# mc.net
KiCad netlist of a schematic drawn in EAGLE
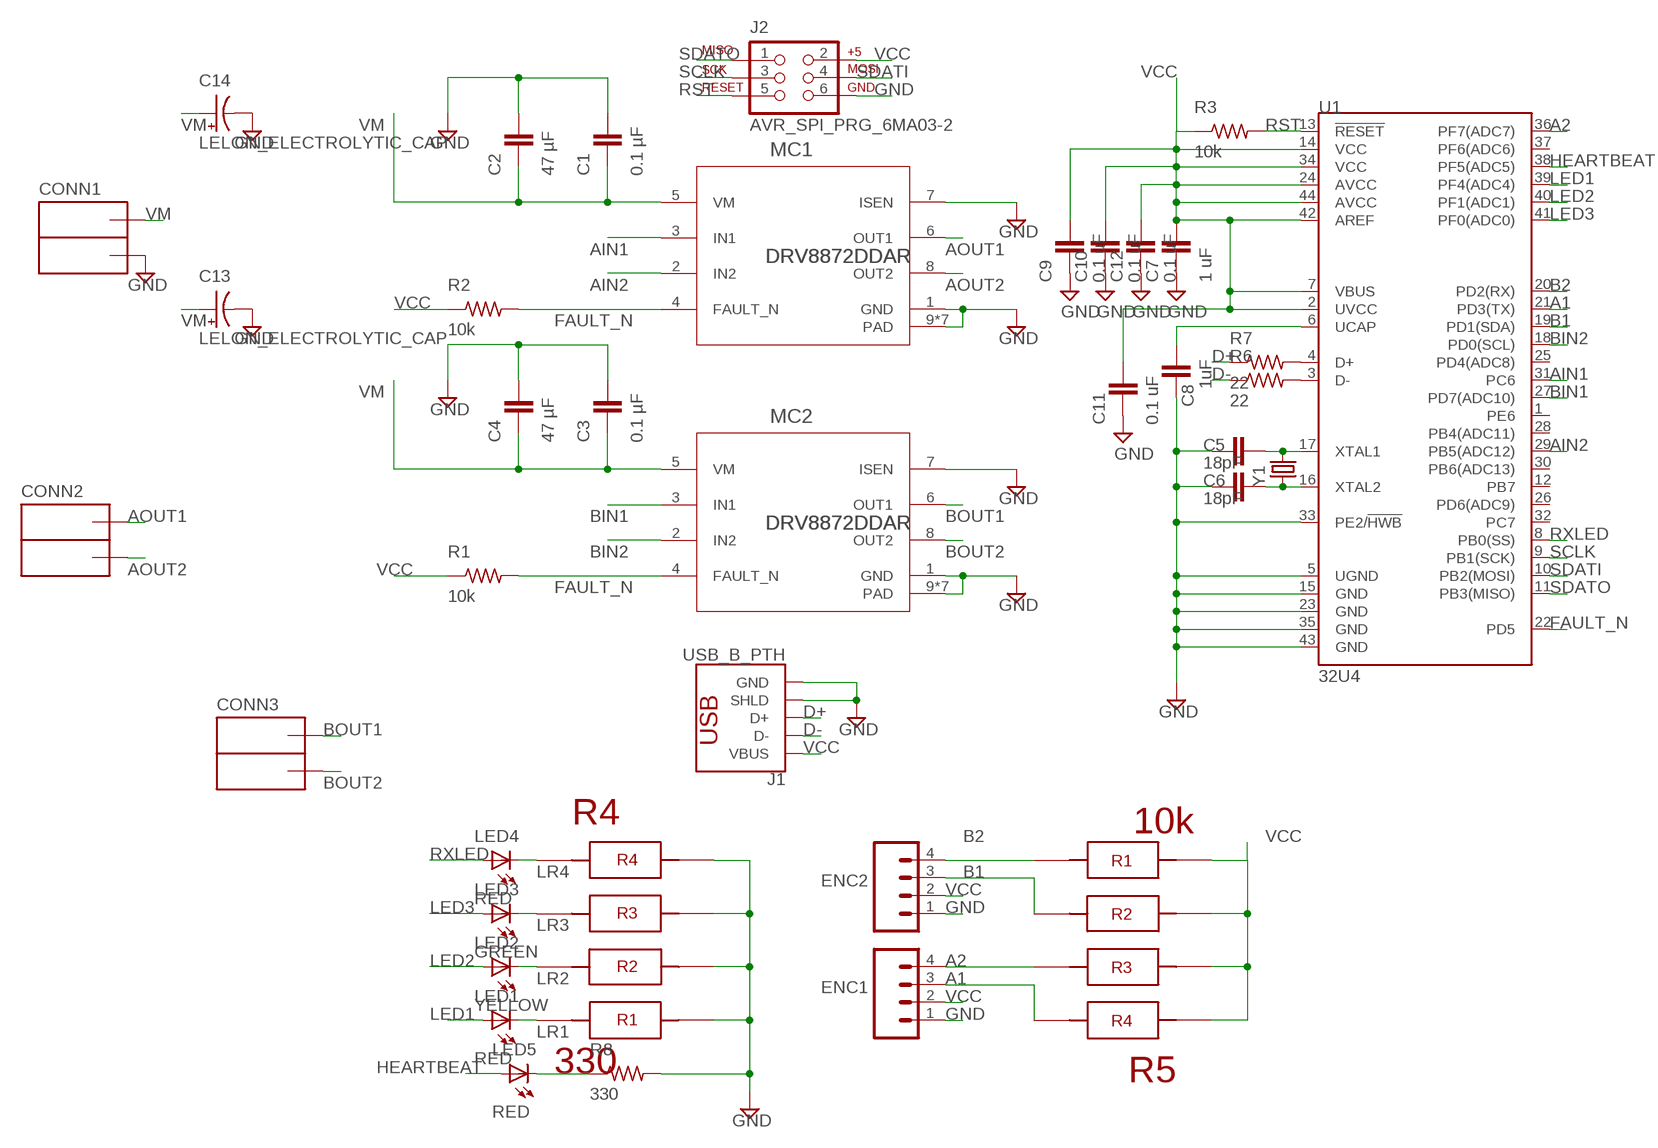
[diagram p0: schematic, sheet 1]

(export (version "E")
  (design (tool "Eeschema 10.0.6"))
  (components
    (comp (ref "C1")
      (value "0.1 µF")
      (footprint "eagle-import:0603-CAP")
      (libsource (lib "eagle-import") (part "CAP0603-CAP"))
    )
    (comp (ref "C2")
      (value "47 µF")
      (footprint "eagle-import:1206")
      (libsource (lib "eagle-import") (part "CAP1206"))
    )
    (comp (ref "C3")
      (value "0.1 µF")
      (footprint "eagle-import:0603-CAP")
      (libsource (lib "eagle-import") (part "CAP0603-CAP"))
    )
    (comp (ref "C4")
      (value "47 µF")
      (footprint "eagle-import:1206")
      (libsource (lib "eagle-import") (part "CAP1206"))
    )
    (comp (ref "C5")
      (value "18pF")
      (footprint "eagle-import:0603-CAP")
      (libsource (lib "eagle-import") (part "CAP0603-CAP"))
    )
    (comp (ref "C6")
      (value "18pF")
      (footprint "eagle-import:0603-CAP")
      (libsource (lib "eagle-import") (part "CAP0603-CAP"))
    )
    (comp (ref "C7")
      (value "1 uF")
      (footprint "eagle-import:0603-CAP")
      (libsource (lib "eagle-import") (part "CAP0603-CAP"))
    )
    (comp (ref "C8")
      (value "1uF")
      (footprint "eagle-import:0603-CAP")
      (libsource (lib "eagle-import") (part "CAP0603-CAP"))
    )
    (comp (ref "C9")
      (value "0.1 uF")
      (footprint "eagle-import:0402-CAP")
      (libsource (lib "eagle-import") (part "CAP0402-CAP"))
    )
    (comp (ref "C10")
      (value "0.1 uF")
      (footprint "eagle-import:0402-CAP")
      (libsource (lib "eagle-import") (part "CAP0402-CAP"))
    )
    (comp (ref "C11")
      (value "0.1 uF")
      (footprint "eagle-import:0402-CAP")
      (libsource (lib "eagle-import") (part "CAP0402-CAP"))
    )
    (comp (ref "C12")
      (value "0.1 uF")
      (footprint "eagle-import:0402-CAP")
      (libsource (lib "eagle-import") (part "CAP0402-CAP"))
    )
    (comp (ref "C13")
      (value "LELON_ELECTROLYTIC_CAP")
      (footprint "eagle-import:LELON_CAP")
      (libsource (lib "eagle-import") (part "LELON_ELECTROLYTIC_CAP"))
    )
    (comp (ref "C14")
      (value "LELON_ELECTROLYTIC_CAP")
      (footprint "eagle-import:LELON_CAP")
      (libsource (lib "eagle-import") (part "LELON_ELECTROLYTIC_CAP"))
    )
    (comp (ref "CONN1")
      (value "ANDERSONVERTICAL")
      (footprint "eagle-import:ANDERSON_VERTICAL")
      (libsource (lib "eagle-import") (part "ANDERSONVERTICAL"))
    )
    (comp (ref "CONN2")
      (value "ANDERSONVERTICAL")
      (footprint "eagle-import:ANDERSON_VERTICAL")
      (libsource (lib "eagle-import") (part "ANDERSONVERTICAL"))
    )
    (comp (ref "CONN3")
      (value "ANDERSONVERTICAL")
      (footprint "eagle-import:ANDERSON_VERTICAL")
      (libsource (lib "eagle-import") (part "ANDERSONVERTICAL"))
    )
    (comp (ref "ENC1")
      (value "M041X04-MTA")
      (footprint "eagle-import:1X04-MTA")
      (libsource (lib "eagle-import") (part "M041X04-MTA"))
    )
    (comp (ref "ENC2")
      (value "M041X04-MTA")
      (footprint "eagle-import:1X04-MTA")
      (libsource (lib "eagle-import") (part "M041X04-MTA"))
    )
    (comp (ref "J1")
      (value "USB_B_PTH")
      (footprint "eagle-import:USB-B-PTH")
      (libsource (lib "eagle-import") (part "USB_B_PTH"))
    )
    (comp (ref "J2")
      (value "AVR_SPI_PRG_6MA03-2")
      (footprint "eagle-import:MA03-2")
      (libsource (lib "eagle-import") (part "AVR_SPI_PRG_6MA03-2"))
    )
    (comp (ref "LED1")
      (value "RED")
      (footprint "eagle-import:LED-0805")
      (libsource (lib "eagle-import") (part "LED0805"))
    )
    (comp (ref "LED2")
      (value "YELLOW")
      (footprint "eagle-import:LED-0805")
      (libsource (lib "eagle-import") (part "LED0805"))
    )
    (comp (ref "LED3")
      (value "GREEN")
      (footprint "eagle-import:LED-0805")
      (libsource (lib "eagle-import") (part "LED0805"))
    )
    (comp (ref "LED4")
      (value "RED")
      (footprint "eagle-import:LED-0805")
      (libsource (lib "eagle-import") (part "LED0805"))
    )
    (comp (ref "LED5")
      (value "RED")
      (footprint "eagle-import:LED-0805")
      (libsource (lib "eagle-import") (part "LED0805"))
    )
    (comp (ref "MC1")
      (value "DRV8872DDAR")
      (footprint "eagle-import:DDA0008H_N_TEX")
      (libsource (lib "eagle-import") (part "DRV8872DDAR"))
    )
    (comp (ref "MC2")
      (value "DRV8872DDAR")
      (footprint "eagle-import:DDA0008H_N_TEX")
      (libsource (lib "eagle-import") (part "DRV8872DDAR"))
    )
    (comp (ref "R1")
      (value "10k")
      (footprint "eagle-import:R0603")
      (fields (field (name "MANUFACTURER") "Rohm Semiconductor"))
      (libsource (lib "eagle-import") (part "R-US_R0603"))
    )
    (comp (ref "R2")
      (value "10k")
      (footprint "eagle-import:R0603")
      (fields (field (name "MANUFACTURER") "Rohm Semiconductor"))
      (libsource (lib "eagle-import") (part "R-US_R0603"))
    )
    (comp (ref "R3")
      (value "10k")
      (footprint "eagle-import:R0603")
      (fields (field (name "MANUFACTURER") "Rohm Semiconductor"))
      (libsource (lib "eagle-import") (part "R-US_R0603"))
    )
    (comp (ref "R4")
      (value "330")
      (footprint "eagle-import:4X-0603")
      (libsource (lib "eagle-import") (part "4X-0603"))
    )
    (comp (ref "R5")
      (value "10k")
      (footprint "eagle-import:4X-0603")
      (libsource (lib "eagle-import") (part "4X-0603"))
    )
    (comp (ref "R6")
      (value "22")
      (footprint "eagle-import:R0603")
      (fields (field (name "MANUFACTURER") "Rohm Semiconductor"))
      (libsource (lib "eagle-import") (part "R-US_R0603"))
    )
    (comp (ref "R7")
      (value "22")
      (footprint "eagle-import:R0603")
      (fields (field (name "MANUFACTURER") "Rohm Semiconductor"))
      (libsource (lib "eagle-import") (part "R-US_R0603"))
    )
    (comp (ref "R8")
      (value "330")
      (footprint "eagle-import:R0603")
      (fields (field (name "MANUFACTURER") "Rohm Semiconductor"))
      (libsource (lib "eagle-import") (part "R-US_R0603"))
    )
    (comp (ref "U1")
      (value "32U4")
      (footprint "eagle-import:QFN-44")
      (libsource (lib "eagle-import") (part "ATMEGA32U4QFN"))
    )
    (comp (ref "Y1")
      (value "CRYSTAL")
      (footprint "eagle-import:CRYSTAL-SMD-5.0X3.2-2PIN")
      (libsource (lib "eagle-import") (part "CRYSTAL"))
    )
  )
  (nets
    (net (code "1") (name "/A1") (class "Default")
      (node (ref "ENC1") (pin "3") (pinfunction "3_3") (pintype "passive"))
      (node (ref "R5") (pin "4") (pinfunction "4_4") (pintype "bidirectional"))
      (node (ref "U1") (pin "21") (pinfunction "PD3(TX)_21") (pintype "bidirectional"))
    )
    (net (code "2") (name "/A2") (class "Default")
      (node (ref "ENC1") (pin "4") (pinfunction "4_4") (pintype "passive"))
      (node (ref "R5") (pin "3") (pinfunction "3_3") (pintype "bidirectional"))
      (node (ref "U1") (pin "36") (pinfunction "PF7(ADC7)_36") (pintype "bidirectional"))
    )
    (net (code "3") (name "/AIN1") (class "Default")
      (node (ref "MC1") (pin "3") (pinfunction "IN1_3") (pintype "input"))
      (node (ref "U1") (pin "31") (pinfunction "PC6_31") (pintype "bidirectional"))
    )
    (net (code "4") (name "/AIN2") (class "Default")
      (node (ref "MC1") (pin "2") (pinfunction "IN2_2") (pintype "input"))
      (node (ref "U1") (pin "29") (pinfunction "PB5(ADC12)_29") (pintype "bidirectional"))
    )
    (net (code "5") (name "/AOUT1") (class "Default")
      (node (ref "CONN2") (pin "PIN2") (pinfunction "OUTA_PIN2") (pintype "bidirectional"))
      (node (ref "MC1") (pin "6") (pinfunction "OUT1_6") (pintype "output"))
    )
    (net (code "6") (name "/AOUT2") (class "Default")
      (node (ref "CONN2") (pin "PIN1") (pinfunction "OUTB_PIN1") (pintype "bidirectional"))
      (node (ref "MC1") (pin "8") (pinfunction "OUT2_8") (pintype "output"))
    )
    (net (code "7") (name "/B1") (class "Default")
      (node (ref "ENC2") (pin "3") (pinfunction "3_3") (pintype "passive"))
      (node (ref "R5") (pin "2") (pinfunction "2_2") (pintype "bidirectional"))
      (node (ref "U1") (pin "19") (pinfunction "PD1(SDA)_19") (pintype "bidirectional"))
    )
    (net (code "8") (name "/B2") (class "Default")
      (node (ref "ENC2") (pin "4") (pinfunction "4_4") (pintype "passive"))
      (node (ref "R5") (pin "1") (pinfunction "1_1") (pintype "bidirectional"))
      (node (ref "U1") (pin "20") (pinfunction "PD2(RX)_20") (pintype "bidirectional"))
    )
    (net (code "9") (name "/BIN1") (class "Default")
      (node (ref "MC2") (pin "3") (pinfunction "IN1_3") (pintype "input"))
      (node (ref "U1") (pin "27") (pinfunction "PD7(ADC10)_27") (pintype "bidirectional"))
    )
    (net (code "10") (name "/BIN2") (class "Default")
      (node (ref "MC2") (pin "2") (pinfunction "IN2_2") (pintype "input"))
      (node (ref "U1") (pin "18") (pinfunction "PD0(SCL)_18") (pintype "bidirectional"))
    )
    (net (code "11") (name "/BOUT1") (class "Default")
      (node (ref "CONN3") (pin "PIN2") (pinfunction "OUTA_PIN2") (pintype "bidirectional"))
      (node (ref "MC2") (pin "6") (pinfunction "OUT1_6") (pintype "output"))
    )
    (net (code "12") (name "/BOUT2") (class "Default")
      (node (ref "CONN3") (pin "PIN1") (pinfunction "OUTB_PIN1") (pintype "bidirectional"))
      (node (ref "MC2") (pin "8") (pinfunction "OUT2_8") (pintype "output"))
    )
    (net (code "13") (name "/D+") (class "Default")
      (node (ref "J1") (pin "D+") (pinfunction "D+_D+") (pintype "bidirectional"))
      (node (ref "R7") (pin "1") (pinfunction "1_1") (pintype "passive"))
    )
    (net (code "14") (name "/D-") (class "Default")
      (node (ref "J1") (pin "D-") (pinfunction "D-_D-") (pintype "bidirectional"))
      (node (ref "R6") (pin "1") (pinfunction "1_1") (pintype "passive"))
    )
    (net (code "15") (name "/FAULT_N") (class "Default")
      (node (ref "MC1") (pin "4") (pinfunction "FAULT_N_4") (pintype "open_collector"))
      (node (ref "MC2") (pin "4") (pinfunction "FAULT_N_4") (pintype "open_collector"))
      (node (ref "R1") (pin "2") (pinfunction "2_2") (pintype "passive"))
      (node (ref "R2") (pin "2") (pinfunction "2_2") (pintype "passive"))
      (node (ref "U1") (pin "22") (pinfunction "PD5_22") (pintype "bidirectional"))
    )
    (net (code "16") (name "/HEARTBEAT") (class "Default")
      (node (ref "LED5") (pin "A") (pinfunction "A_A") (pintype "passive"))
      (node (ref "U1") (pin "38") (pinfunction "PF5(ADC5)_38") (pintype "bidirectional"))
    )
    (net (code "17") (name "/LED1") (class "Default")
      (node (ref "LED1") (pin "A") (pinfunction "A_A") (pintype "passive"))
      (node (ref "U1") (pin "39") (pinfunction "PF4(ADC4)_39") (pintype "bidirectional"))
    )
    (net (code "18") (name "/LED2") (class "Default")
      (node (ref "LED2") (pin "A") (pinfunction "A_A") (pintype "passive"))
      (node (ref "U1") (pin "40") (pinfunction "PF1(ADC1)_40") (pintype "bidirectional"))
    )
    (net (code "19") (name "/LED3") (class "Default")
      (node (ref "LED3") (pin "A") (pinfunction "A_A") (pintype "passive"))
      (node (ref "U1") (pin "41") (pinfunction "PF0(ADC0)_41") (pintype "bidirectional"))
    )
    (net (code "20") (name "/LR1") (class "Default")
      (node (ref "LED1") (pin "C") (pinfunction "C_C") (pintype "passive"))
      (node (ref "R4") (pin "8") (pinfunction "8_8") (pintype "bidirectional"))
    )
    (net (code "21") (name "/LR2") (class "Default")
      (node (ref "LED2") (pin "C") (pinfunction "C_C") (pintype "passive"))
      (node (ref "R4") (pin "7") (pinfunction "7_7") (pintype "bidirectional"))
    )
    (net (code "22") (name "/LR3") (class "Default")
      (node (ref "LED3") (pin "C") (pinfunction "C_C") (pintype "passive"))
      (node (ref "R4") (pin "6") (pinfunction "6_6") (pintype "bidirectional"))
    )
    (net (code "23") (name "/LR4") (class "Default")
      (node (ref "LED4") (pin "C") (pinfunction "C_C") (pintype "passive"))
      (node (ref "R4") (pin "5") (pinfunction "5_5") (pintype "bidirectional"))
    )
    (net (code "24") (name "/RST") (class "Default")
      (node (ref "J2") (pin "5") (pinfunction "5_5") (pintype "passive"))
      (node (ref "R3") (pin "2") (pinfunction "2_2") (pintype "passive"))
      (node (ref "U1") (pin "13") (pinfunction "~{RESET}_13") (pintype "bidirectional"))
    )
    (net (code "25") (name "/RXLED") (class "Default")
      (node (ref "LED4") (pin "A") (pinfunction "A_A") (pintype "passive"))
      (node (ref "U1") (pin "8") (pinfunction "PB0(SS)_8") (pintype "bidirectional"))
    )
    (net (code "26") (name "/SCLK") (class "Default")
      (node (ref "J2") (pin "3") (pinfunction "3_3") (pintype "passive"))
      (node (ref "U1") (pin "9") (pinfunction "PB1(SCK)_9") (pintype "bidirectional"))
    )
    (net (code "27") (name "/SDATI") (class "Default")
      (node (ref "J2") (pin "4") (pinfunction "4_4") (pintype "passive"))
      (node (ref "U1") (pin "10") (pinfunction "PB2(MOSI)_10") (pintype "bidirectional"))
    )
    (net (code "28") (name "/SDATO") (class "Default")
      (node (ref "J2") (pin "1") (pinfunction "1_1") (pintype "passive"))
      (node (ref "U1") (pin "11") (pinfunction "PB3(MISO)_11") (pintype "bidirectional"))
    )
    (net (code "29") (name "/VCC") (class "Default")
      (node (ref "C10") (pin "2") (pinfunction "2_2") (pintype "passive"))
      (node (ref "C11") (pin "2") (pinfunction "2_2") (pintype "passive"))
      (node (ref "C12") (pin "2") (pinfunction "2_2") (pintype "passive"))
      (node (ref "C7") (pin "2") (pinfunction "2_2") (pintype "passive"))
      (node (ref "C9") (pin "2") (pinfunction "2_2") (pintype "passive"))
      (node (ref "ENC1") (pin "2") (pinfunction "2_2") (pintype "passive"))
      (node (ref "ENC2") (pin "2") (pinfunction "2_2") (pintype "passive"))
      (node (ref "J1") (pin "VBUS") (pinfunction "VBUS_VBUS") (pintype "power_in"))
      (node (ref "J2") (pin "2") (pinfunction "2_2") (pintype "passive"))
      (node (ref "R1") (pin "1") (pinfunction "1_1") (pintype "passive"))
      (node (ref "R2") (pin "1") (pinfunction "1_1") (pintype "passive"))
      (node (ref "R3") (pin "1") (pinfunction "1_1") (pintype "passive"))
      (node (ref "R5") (pin "5") (pinfunction "5_5") (pintype "bidirectional"))
      (node (ref "R5") (pin "6") (pinfunction "6_6") (pintype "bidirectional"))
      (node (ref "R5") (pin "7") (pinfunction "7_7") (pintype "bidirectional"))
      (node (ref "R5") (pin "8") (pinfunction "8_8") (pintype "bidirectional"))
      (node (ref "U1") (pin "14") (pinfunction "VCC_14") (pintype "bidirectional"))
      (node (ref "U1") (pin "2") (pinfunction "UVCC_2") (pintype "bidirectional"))
      (node (ref "U1") (pin "24") (pinfunction "AVCC_24") (pintype "bidirectional"))
      (node (ref "U1") (pin "34") (pinfunction "VCC_34") (pintype "bidirectional"))
      (node (ref "U1") (pin "42") (pinfunction "AREF_42") (pintype "bidirectional"))
      (node (ref "U1") (pin "44") (pinfunction "AVCC_44") (pintype "bidirectional"))
      (node (ref "U1") (pin "7") (pinfunction "VBUS_7") (pintype "bidirectional"))
    )
    (net (code "30") (name "/VM") (class "Default")
      (node (ref "C1") (pin "1") (pinfunction "1_1") (pintype "passive"))
      (node (ref "C13") (pin "P$1") (pinfunction "+_P$1") (pintype "passive"))
      (node (ref "C14") (pin "P$1") (pinfunction "+_P$1") (pintype "passive"))
      (node (ref "C2") (pin "1") (pinfunction "1_1") (pintype "passive"))
      (node (ref "C3") (pin "1") (pinfunction "1_1") (pintype "passive"))
      (node (ref "C4") (pin "1") (pinfunction "1_1") (pintype "passive"))
      (node (ref "CONN1") (pin "PIN2") (pinfunction "OUTA_PIN2") (pintype "bidirectional"))
      (node (ref "MC1") (pin "5") (pinfunction "VM_5") (pintype "power_in"))
      (node (ref "MC2") (pin "5") (pinfunction "VM_5") (pintype "power_in"))
    )
    (net (code "31") (name "GND") (class "Default")
      (node (ref "C1") (pin "2") (pinfunction "2_2") (pintype "passive"))
      (node (ref "C10") (pin "1") (pinfunction "1_1") (pintype "passive"))
      (node (ref "C11") (pin "1") (pinfunction "1_1") (pintype "passive"))
      (node (ref "C12") (pin "1") (pinfunction "1_1") (pintype "passive"))
      (node (ref "C13") (pin "P$2") (pinfunction "-_P$2") (pintype "passive"))
      (node (ref "C14") (pin "P$2") (pinfunction "-_P$2") (pintype "passive"))
      (node (ref "C2") (pin "2") (pinfunction "2_2") (pintype "passive"))
      (node (ref "C3") (pin "2") (pinfunction "2_2") (pintype "passive"))
      (node (ref "C4") (pin "2") (pinfunction "2_2") (pintype "passive"))
      (node (ref "C5") (pin "1") (pinfunction "1_1") (pintype "passive"))
      (node (ref "C6") (pin "1") (pinfunction "1_1") (pintype "passive"))
      (node (ref "C7") (pin "1") (pinfunction "1_1") (pintype "passive"))
      (node (ref "C8") (pin "1") (pinfunction "1_1") (pintype "passive"))
      (node (ref "C9") (pin "1") (pinfunction "1_1") (pintype "passive"))
      (node (ref "CONN1") (pin "PIN1") (pinfunction "OUTB_PIN1") (pintype "bidirectional"))
      (node (ref "ENC1") (pin "1") (pinfunction "1_1") (pintype "passive"))
      (node (ref "ENC2") (pin "1") (pinfunction "1_1") (pintype "passive"))
      (node (ref "J1") (pin "GND") (pinfunction "GND_GND") (pintype "power_in"))
      (node (ref "J1") (pin "SHLD1") (pinfunction "SHLD_SHLD1") (pintype "bidirectional"))
      (node (ref "J1") (pin "SHLD2") (pinfunction "SHLD_SHLD2") (pintype "bidirectional"))
      (node (ref "J2") (pin "6") (pinfunction "6_6") (pintype "passive"))
      (node (ref "MC1") (pin "1") (pinfunction "GND_1") (pintype "power_in"))
      (node (ref "MC1") (pin "7") (pinfunction "ISEN_7") (pintype "input"))
      (node (ref "MC1") (pin "9") (pinfunction "PAD_9") (pintype "power_in"))
      (node (ref "MC1") (pin "P$1") (pinfunction "PAD_P$1") (pintype "power_in"))
      (node (ref "MC1") (pin "P$2") (pinfunction "PAD_P$2") (pintype "power_in"))
      (node (ref "MC1") (pin "P$3") (pinfunction "PAD_P$3") (pintype "power_in"))
      (node (ref "MC1") (pin "P$4") (pinfunction "PAD_P$4") (pintype "power_in"))
      (node (ref "MC1") (pin "P$5") (pinfunction "PAD_P$5") (pintype "power_in"))
      (node (ref "MC1") (pin "P$6") (pinfunction "PAD_P$6") (pintype "power_in"))
      (node (ref "MC2") (pin "1") (pinfunction "GND_1") (pintype "power_in"))
      (node (ref "MC2") (pin "7") (pinfunction "ISEN_7") (pintype "input"))
      (node (ref "MC2") (pin "9") (pinfunction "PAD_9") (pintype "power_in"))
      (node (ref "MC2") (pin "P$1") (pinfunction "PAD_P$1") (pintype "power_in"))
      (node (ref "MC2") (pin "P$2") (pinfunction "PAD_P$2") (pintype "power_in"))
      (node (ref "MC2") (pin "P$3") (pinfunction "PAD_P$3") (pintype "power_in"))
      (node (ref "MC2") (pin "P$4") (pinfunction "PAD_P$4") (pintype "power_in"))
      (node (ref "MC2") (pin "P$5") (pinfunction "PAD_P$5") (pintype "power_in"))
      (node (ref "MC2") (pin "P$6") (pinfunction "PAD_P$6") (pintype "power_in"))
      (node (ref "R4") (pin "1") (pinfunction "1_1") (pintype "bidirectional"))
      (node (ref "R4") (pin "2") (pinfunction "2_2") (pintype "bidirectional"))
      (node (ref "R4") (pin "3") (pinfunction "3_3") (pintype "bidirectional"))
      (node (ref "R4") (pin "4") (pinfunction "4_4") (pintype "bidirectional"))
      (node (ref "R8") (pin "2") (pinfunction "2_2") (pintype "passive"))
      (node (ref "U1") (pin "15") (pinfunction "GND_15") (pintype "bidirectional"))
      (node (ref "U1") (pin "23") (pinfunction "GND_23") (pintype "bidirectional"))
      (node (ref "U1") (pin "33") (pinfunction "PE2/~{HWB}_33") (pintype "bidirectional"))
      (node (ref "U1") (pin "35") (pinfunction "GND_35") (pintype "bidirectional"))
      (node (ref "U1") (pin "43") (pinfunction "GND_43") (pintype "bidirectional"))
      (node (ref "U1") (pin "5") (pinfunction "UGND_5") (pintype "bidirectional"))
    )
    (net (code "32") (name "Net-(LED5-PadC)") (class "Default")
      (node (ref "LED5") (pin "C") (pinfunction "C_C") (pintype "passive"))
      (node (ref "R8") (pin "1") (pinfunction "1_1") (pintype "passive"))
    )
    (net (code "33") (name "Net-(U1-D+)") (class "Default")
      (node (ref "R7") (pin "2") (pinfunction "2_2") (pintype "passive"))
      (node (ref "U1") (pin "4") (pinfunction "D+_4") (pintype "bidirectional"))
    )
    (net (code "34") (name "Net-(U1-D-)") (class "Default")
      (node (ref "R6") (pin "2") (pinfunction "2_2") (pintype "passive"))
      (node (ref "U1") (pin "3") (pinfunction "D-_3") (pintype "bidirectional"))
    )
    (net (code "35") (name "Net-(U1-UCAP)") (class "Default")
      (node (ref "C8") (pin "2") (pinfunction "2_2") (pintype "passive"))
      (node (ref "U1") (pin "6") (pinfunction "UCAP_6") (pintype "bidirectional"))
    )
    (net (code "36") (name "Net-(U1-XTAL1)") (class "Default")
      (node (ref "C5") (pin "2") (pinfunction "2_2") (pintype "passive"))
      (node (ref "U1") (pin "17") (pinfunction "XTAL1_17") (pintype "bidirectional"))
      (node (ref "Y1") (pin "P$2") (pinfunction "2_P$2") (pintype "passive"))
    )
    (net (code "37") (name "Net-(U1-XTAL2)") (class "Default")
      (node (ref "C6") (pin "2") (pinfunction "2_2") (pintype "passive"))
      (node (ref "U1") (pin "16") (pinfunction "XTAL2_16") (pintype "bidirectional"))
      (node (ref "Y1") (pin "P$1") (pinfunction "1_P$1") (pintype "passive"))
    )
    (net (code "38") (name "unconnected-(U1-PB4(ADC11)-Pad28)") (class "Default")
      (node (ref "U1") (pin "28") (pinfunction "PB4(ADC11)_28") (pintype "bidirectional"))
    )
    (net (code "39") (name "unconnected-(U1-PB6(ADC13)-Pad30)") (class "Default")
      (node (ref "U1") (pin "30") (pinfunction "PB6(ADC13)_30") (pintype "bidirectional"))
    )
    (net (code "40") (name "unconnected-(U1-PB7-Pad12)") (class "Default")
      (node (ref "U1") (pin "12") (pinfunction "PB7_12") (pintype "bidirectional"))
    )
    (net (code "41") (name "unconnected-(U1-PC7-Pad32)") (class "Default")
      (node (ref "U1") (pin "32") (pinfunction "PC7_32") (pintype "bidirectional"))
    )
    (net (code "42") (name "unconnected-(U1-PD4(ADC8)-Pad25)") (class "Default")
      (node (ref "U1") (pin "25") (pinfunction "PD4(ADC8)_25") (pintype "bidirectional"))
    )
    (net (code "43") (name "unconnected-(U1-PD6(ADC9)-Pad26)") (class "Default")
      (node (ref "U1") (pin "26") (pinfunction "PD6(ADC9)_26") (pintype "bidirectional"))
    )
    (net (code "44") (name "unconnected-(U1-PE6-Pad1)") (class "Default")
      (node (ref "U1") (pin "1") (pinfunction "PE6_1") (pintype "bidirectional"))
    )
    (net (code "45") (name "unconnected-(U1-PF6(ADC6)-Pad37)") (class "Default")
      (node (ref "U1") (pin "37") (pinfunction "PF6(ADC6)_37") (pintype "bidirectional"))
    )
  )
)
